# SIM900_schematic.net
KiCad netlist of a schematic drawn in EAGLE
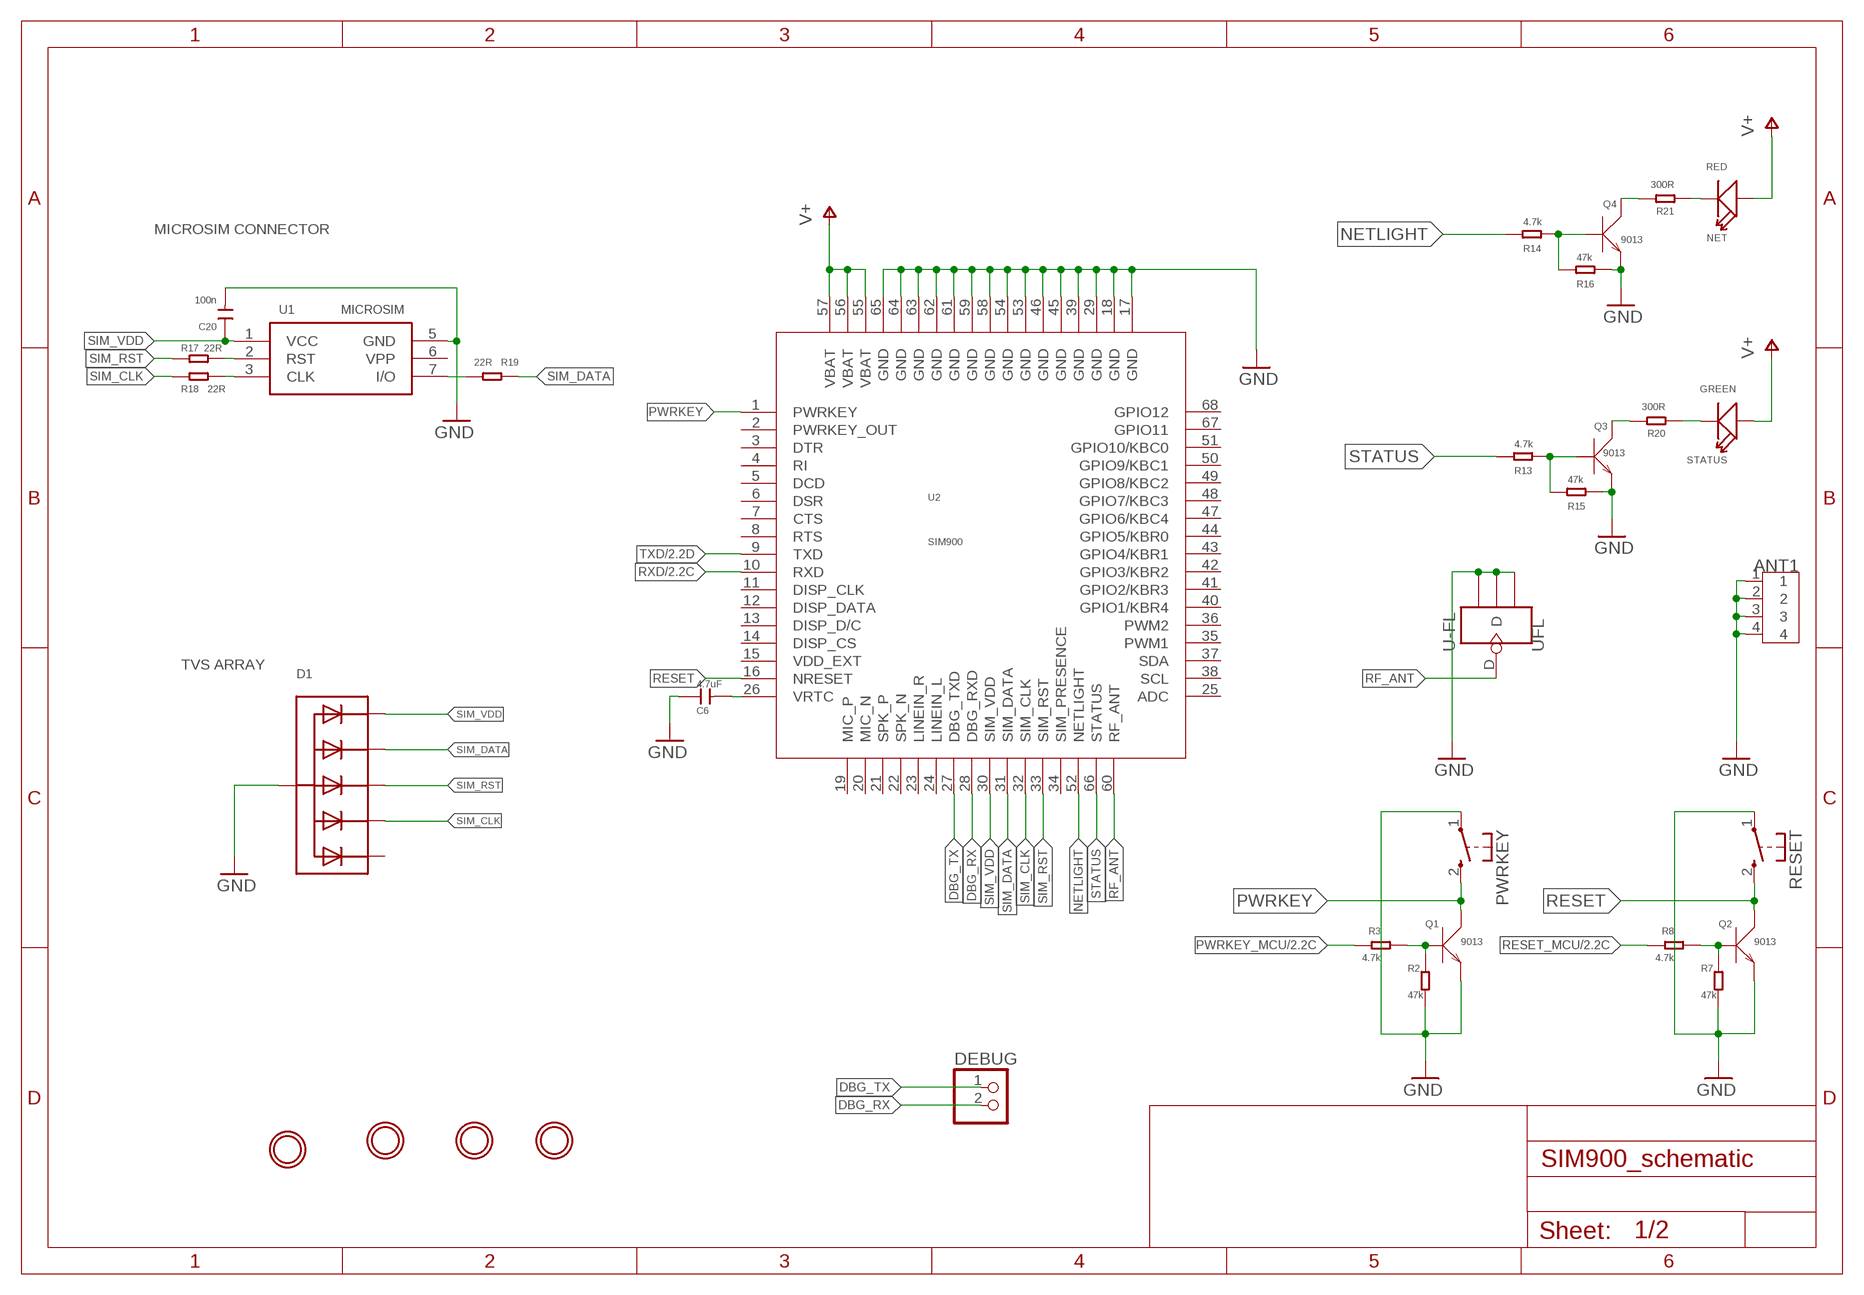
[diagram p0: schematic, sheet 1]
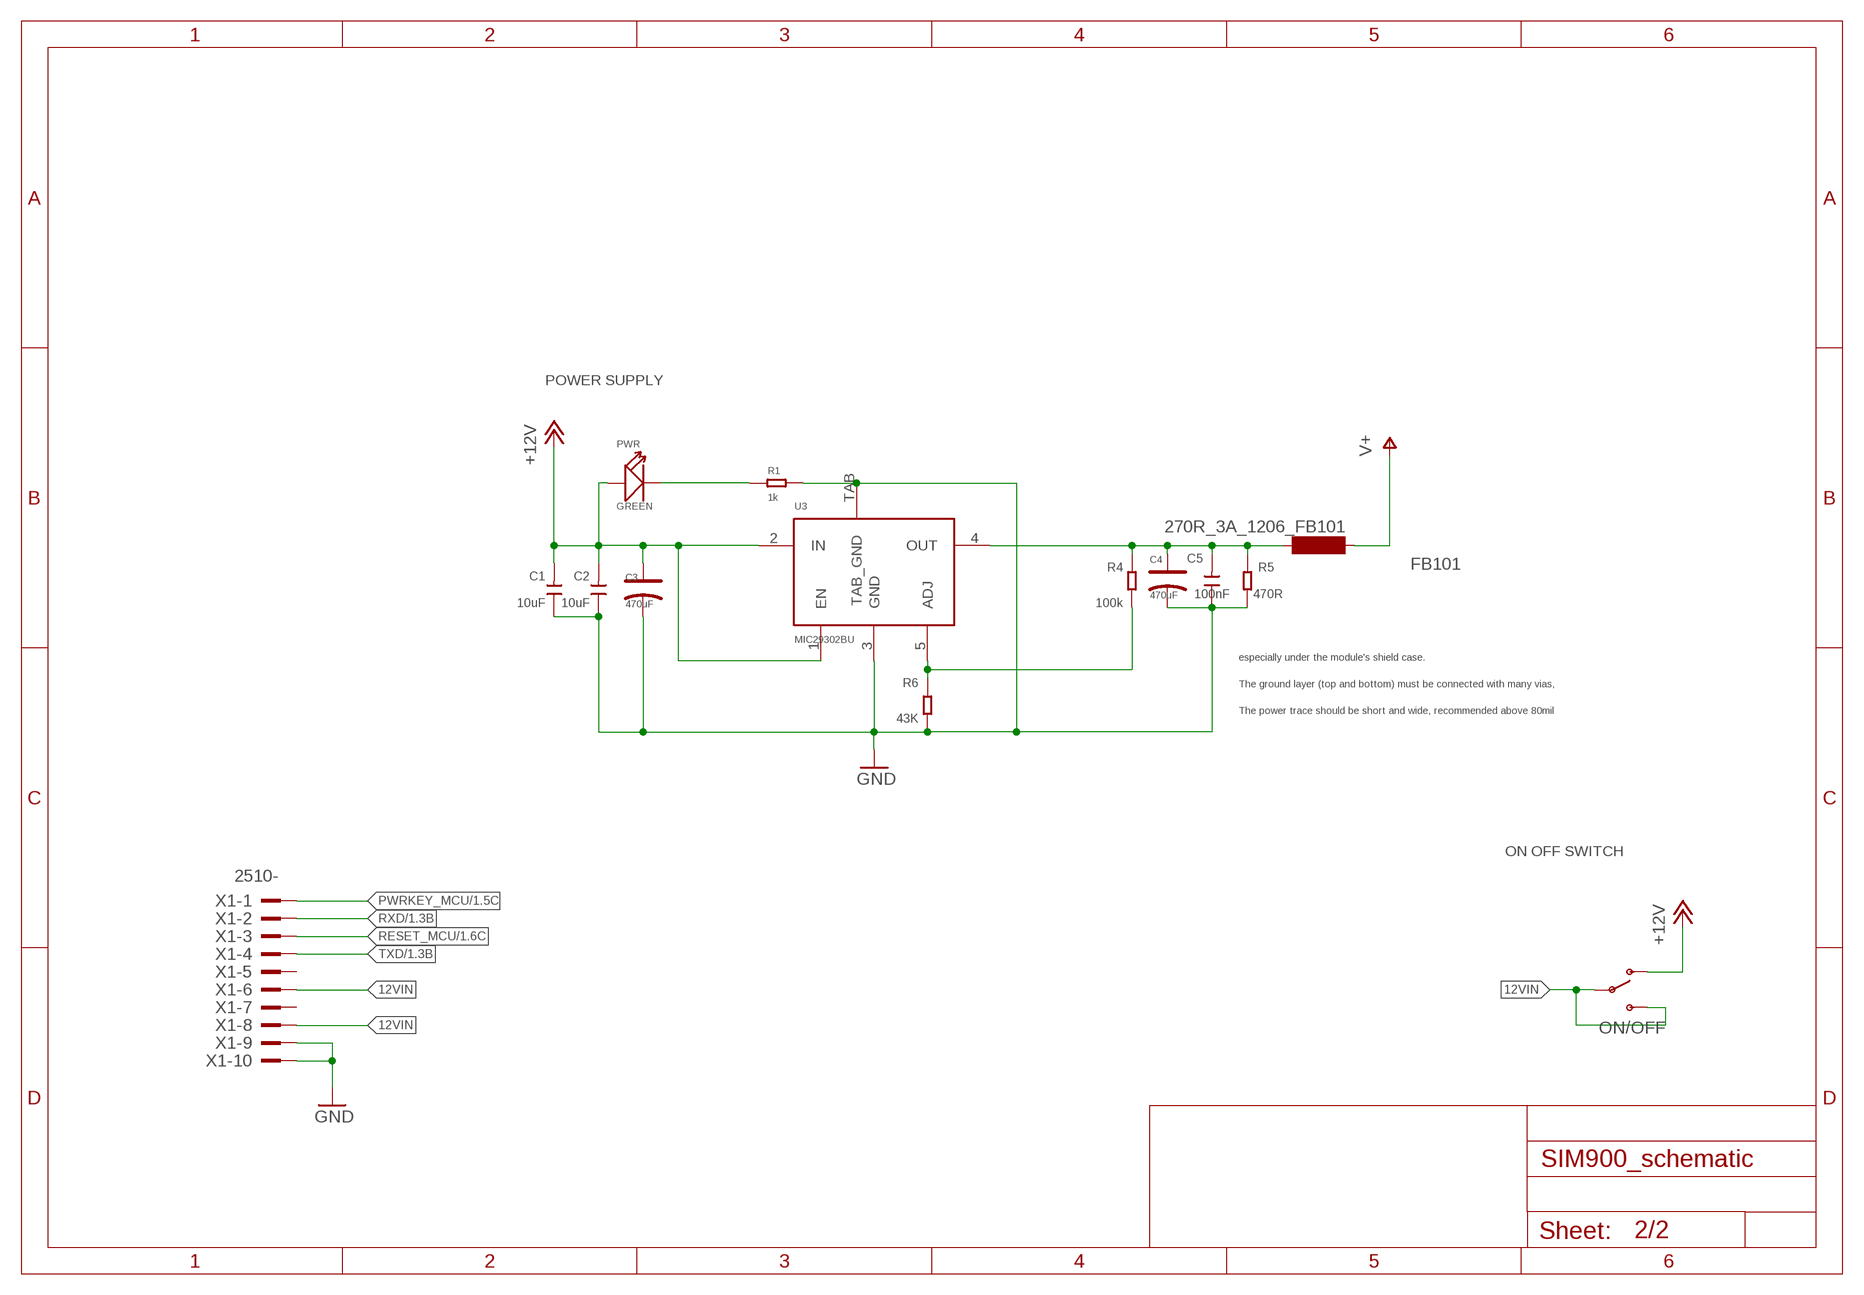
[diagram p1: schematic, sheet 2]

(export (version "E")
  (design (tool "Eeschema 10.0.6"))
  (components
    (comp (ref "C1")
      (value "10uF")
      (footprint "eagle-import:0805")
      (libsource (lib "eagle-import") (part "C-0805"))
    )
    (comp (ref "C2")
      (value "10uF")
      (footprint "eagle-import:0805")
      (libsource (lib "eagle-import") (part "C-0805"))
    )
    (comp (ref "C3")
      (value "470uF")
      (footprint "eagle-import:AVX_D")
      (libsource (lib "eagle-import") (part "006-CAP_AVX_D"))
    )
    (comp (ref "C4")
      (value "470uF")
      (footprint "eagle-import:AVX_D")
      (libsource (lib "eagle-import") (part "006-CAP_AVX_D"))
    )
    (comp (ref "C5")
      (value "100nF")
      (footprint "eagle-import:0805")
      (libsource (lib "eagle-import") (part "C-0805"))
    )
    (comp (ref "FB101")
      (value "270R_3A_1206_FB101")
      (footprint "eagle-import:SM-1206")
      (libsource (lib "eagle-import") (part "SM-1206"))
    )
    (comp (ref "ON/OFF")
      (value "SWITCH-SPDTPTH")
      (footprint "eagle-import:SWITCH-SPDT")
      (libsource (lib "eagle-import") (part "SWITCH-SPDTPTH"))
    )
    (comp (ref "PWR")
      (value "GREEN")
      (footprint "eagle-import:D0805")
      (libsource (lib "eagle-import") (part "007-LED0805"))
    )
    (comp (ref "R1")
      (value "1k")
      (footprint "eagle-import:0805")
      (libsource (lib "eagle-import") (part "R-0805"))
    )
    (comp (ref "R4")
      (value "100k")
      (footprint "eagle-import:0805")
      (libsource (lib "eagle-import") (part "R-0805"))
    )
    (comp (ref "R5")
      (value "470R")
      (footprint "eagle-import:0805")
      (libsource (lib "eagle-import") (part "R-0805"))
    )
    (comp (ref "R6")
      (value "43K")
      (footprint "eagle-import:0805")
      (libsource (lib "eagle-import") (part "R-0805"))
    )
    (comp (ref "U3")
      (value "MIC29302BU")
      (footprint "eagle-import:TO-263")
      (libsource (lib "eagle-import") (part "MIC29302BU"))
    )
    (comp (ref "X1")
      (value "2510-")
      (footprint "eagle-import:PAK100_2500-10")
      (fields (field (name "MF") "3M") (field (name "MPN") "2510-6002UB"))
      (libsource (lib "eagle-import") (part "2510-"))
    )
    (comp (ref "ANT1")
      (value "ANTENNA-SMA-IPX")
      (footprint "eagle-import:SMA-TO-IPX")
      (libsource (lib "eagle-import") (part "ANTENNA-SMA-IPX"))
    )
    (comp (ref "C6")
      (value "4.7uF")
      (footprint "eagle-import:0805")
      (libsource (lib "eagle-import") (part "C-0805"))
    )
    (comp (ref "C20")
      (value "100n")
      (footprint "eagle-import:0805")
      (libsource (lib "eagle-import") (part "C-0805"))
    )
    (comp (ref "D1")
      (value "TVSARRAY_5LANE")
      (footprint "eagle-import:SOT363")
      (libsource (lib "eagle-import") (part "TVSARRAY_5LANE"))
    )
    (comp (ref "DEBUG")
      (value "PINHD-1X2")
      (footprint "eagle-import:1X02")
      (libsource (lib "eagle-import") (part "PINHD-1X2"))
    )
    (comp (ref "NET")
      (value "RED")
      (footprint "eagle-import:LED-0805")
      (libsource (lib "eagle-import") (part "LED'0805'"))
    )
    (comp (ref "PWRKEY")
      (value "KSS-2EG4430")
      (footprint "eagle-import:KSS-2EG4430")
      (libsource (lib "eagle-import") (part "KSS-2EG4430"))
    )
    (comp (ref "Q1")
      (value "9013")
      (footprint "eagle-import:SOT23")
      (libsource (lib "eagle-import") (part "TRANSISTOR-NPN-SOT23"))
    )
    (comp (ref "Q2")
      (value "9013")
      (footprint "eagle-import:SOT23")
      (libsource (lib "eagle-import") (part "TRANSISTOR-NPN-SOT23"))
    )
    (comp (ref "Q3")
      (value "9013")
      (footprint "eagle-import:SOT23")
      (libsource (lib "eagle-import") (part "TRANSISTOR-NPN-SOT23"))
    )
    (comp (ref "Q4")
      (value "9013")
      (footprint "eagle-import:SOT23")
      (libsource (lib "eagle-import") (part "TRANSISTOR-NPN-SOT23"))
    )
    (comp (ref "R2")
      (value "47k")
      (footprint "eagle-import:0805")
      (libsource (lib "eagle-import") (part "R-0805"))
    )
    (comp (ref "R3")
      (value "4.7k")
      (footprint "eagle-import:0805")
      (libsource (lib "eagle-import") (part "R-0805"))
    )
    (comp (ref "R7")
      (value "47k")
      (footprint "eagle-import:0805")
      (libsource (lib "eagle-import") (part "R-0805"))
    )
    (comp (ref "R8")
      (value "4.7k")
      (footprint "eagle-import:0805")
      (libsource (lib "eagle-import") (part "R-0805"))
    )
    (comp (ref "R13")
      (value "4.7k")
      (footprint "eagle-import:0805")
      (libsource (lib "eagle-import") (part "R-0805"))
    )
    (comp (ref "R14")
      (value "4.7k")
      (footprint "eagle-import:0805")
      (libsource (lib "eagle-import") (part "R-0805"))
    )
    (comp (ref "R15")
      (value "47k")
      (footprint "eagle-import:0805")
      (libsource (lib "eagle-import") (part "R-0805"))
    )
    (comp (ref "R16")
      (value "47k")
      (footprint "eagle-import:0805")
      (libsource (lib "eagle-import") (part "R-0805"))
    )
    (comp (ref "R17")
      (value "22R")
      (footprint "eagle-import:0805")
      (libsource (lib "eagle-import") (part "R-0805"))
    )
    (comp (ref "R18")
      (value "22R")
      (footprint "eagle-import:0805")
      (libsource (lib "eagle-import") (part "R-0805"))
    )
    (comp (ref "R19")
      (value "22R")
      (footprint "eagle-import:0805")
      (libsource (lib "eagle-import") (part "R-0805"))
    )
    (comp (ref "R20")
      (value "300R")
      (footprint "eagle-import:0805")
      (libsource (lib "eagle-import") (part "R-0805"))
    )
    (comp (ref "R21")
      (value "300R")
      (footprint "eagle-import:0805")
      (libsource (lib "eagle-import") (part "R-0805"))
    )
    (comp (ref "RESET")
      (value "KSS-2EG4430")
      (footprint "eagle-import:KSS-2EG4430")
      (libsource (lib "eagle-import") (part "KSS-2EG4430"))
    )
    (comp (ref "STATUS")
      (value "GREEN")
      (footprint "eagle-import:LED-0805")
      (libsource (lib "eagle-import") (part "LED'0805'"))
    )
    (comp (ref "U$1")
      (value "MOUNTINGHOLE3.0THIN")
      (footprint "eagle-import:MOUNTINGHOLE_3.0_PLATEDTHIN")
      (libsource (lib "eagle-import") (part "MOUNTINGHOLE3.0THIN"))
    )
    (comp (ref "U$2")
      (value "MOUNTINGHOLE3.0THIN")
      (footprint "eagle-import:MOUNTINGHOLE_3.0_PLATEDTHIN")
      (libsource (lib "eagle-import") (part "MOUNTINGHOLE3.0THIN"))
    )
    (comp (ref "U$3")
      (value "MOUNTINGHOLE3.0THIN")
      (footprint "eagle-import:MOUNTINGHOLE_3.0_PLATEDTHIN")
      (libsource (lib "eagle-import") (part "MOUNTINGHOLE3.0THIN"))
    )
    (comp (ref "U$4")
      (value "MOUNTINGHOLE3.0THIN")
      (footprint "eagle-import:MOUNTINGHOLE_3.0_PLATEDTHIN")
      (libsource (lib "eagle-import") (part "MOUNTINGHOLE3.0THIN"))
    )
    (comp (ref "U1")
      (value "MICROSIM")
      (footprint "eagle-import:MICROSIM")
      (libsource (lib "eagle-import") (part "MICROSIM"))
    )
    (comp (ref "U2")
      (value "SIM900")
      (footprint "eagle-import:SIM900")
      (libsource (lib "eagle-import") (part "SIM900"))
    )
    (comp (ref "UFL")
      (value "U-FL")
      (footprint "eagle-import:4P-U-FL")
      (libsource (lib "eagle-import") (part "ANTENNA-U-FL"))
    )
  )
  (nets
    (net (code "1") (name "+12V") (class "Default")
      (node (ref "C1") (pin "2") (pinfunction "2_2") (pintype "passive"))
      (node (ref "C2") (pin "2") (pinfunction "2_2") (pintype "passive"))
      (node (ref "C3") (pin "+") (pinfunction "+_+") (pintype "passive"))
      (node (ref "ON/OFF") (pin "1") (pinfunction "O_1") (pintype "passive"))
      (node (ref "PWR") (pin "+") (pinfunction "+_+") (pintype "passive"))
      (node (ref "U3") (pin "1") (pinfunction "EN_1") (pintype "bidirectional"))
      (node (ref "U3") (pin "2") (pinfunction "IN_2") (pintype "bidirectional"))
    )
    (net (code "2") (name "12VIN") (class "Default")
      (node (ref "ON/OFF") (pin "2") (pinfunction "P_2") (pintype "passive"))
      (node (ref "ON/OFF") (pin "3") (pinfunction "S_3") (pintype "passive"))
      (node (ref "X1") (pin "6") (pinfunction "KL_6") (pintype "passive"))
      (node (ref "X1") (pin "8") (pinfunction "KL_8") (pintype "passive"))
    )
    (net (code "3") (name "DBG_RX") (class "Default")
      (node (ref "DEBUG") (pin "2") (pinfunction "2_2") (pintype "passive"))
      (node (ref "U2") (pin "28") (pinfunction "DBG_RXD_28") (pintype "input"))
    )
    (net (code "4") (name "DBG_TX") (class "Default")
      (node (ref "DEBUG") (pin "1") (pinfunction "1_1") (pintype "passive"))
      (node (ref "U2") (pin "27") (pinfunction "DBG_TXD_27") (pintype "output"))
    )
    (net (code "5") (name "GND") (class "Default")
      (node (ref "ANT1") (pin "1") (pinfunction "1_1") (pintype "bidirectional"))
      (node (ref "ANT1") (pin "2") (pinfunction "2_2") (pintype "bidirectional"))
      (node (ref "ANT1") (pin "3") (pinfunction "3_3") (pintype "bidirectional"))
      (node (ref "ANT1") (pin "4") (pinfunction "4_4") (pintype "bidirectional"))
      (node (ref "C1") (pin "1") (pinfunction "1_1") (pintype "passive"))
      (node (ref "C2") (pin "1") (pinfunction "1_1") (pintype "passive"))
      (node (ref "C20") (pin "2") (pinfunction "2_2") (pintype "passive"))
      (node (ref "C3") (pin "-") (pinfunction "-_-") (pintype "passive"))
      (node (ref "C4") (pin "-") (pinfunction "-_-") (pintype "passive"))
      (node (ref "C5") (pin "1") (pinfunction "1_1") (pintype "passive"))
      (node (ref "C6") (pin "1") (pinfunction "1_1") (pintype "passive"))
      (node (ref "D1") (pin "2") (pinfunction "A_2") (pintype "passive"))
      (node (ref "PWRKEY") (pin "1") (pinfunction "P_1") (pintype "passive"))
      (node (ref "Q1") (pin "2") (pinfunction "E_2") (pintype "passive"))
      (node (ref "Q2") (pin "2") (pinfunction "E_2") (pintype "passive"))
      (node (ref "Q3") (pin "2") (pinfunction "E_2") (pintype "passive"))
      (node (ref "Q4") (pin "2") (pinfunction "E_2") (pintype "passive"))
      (node (ref "R1") (pin "2") (pinfunction "2_2") (pintype "passive"))
      (node (ref "R15") (pin "2") (pinfunction "2_2") (pintype "passive"))
      (node (ref "R16") (pin "2") (pinfunction "2_2") (pintype "passive"))
      (node (ref "R2") (pin "2") (pinfunction "2_2") (pintype "passive"))
      (node (ref "R5") (pin "1") (pinfunction "1_1") (pintype "passive"))
      (node (ref "R6") (pin "1") (pinfunction "1_1") (pintype "passive"))
      (node (ref "R7") (pin "2") (pinfunction "2_2") (pintype "passive"))
      (node (ref "RESET") (pin "1") (pinfunction "P_1") (pintype "passive"))
      (node (ref "U1") (pin "5") (pinfunction "GND_5") (pintype "bidirectional"))
      (node (ref "U2") (pin "17") (pinfunction "GND_17") (pintype "power_in"))
      (node (ref "U2") (pin "18") (pinfunction "GND_18") (pintype "power_in"))
      (node (ref "U2") (pin "29") (pinfunction "GND_29") (pintype "power_in"))
      (node (ref "U2") (pin "39") (pinfunction "GND_39") (pintype "power_in"))
      (node (ref "U2") (pin "45") (pinfunction "GND_45") (pintype "power_in"))
      (node (ref "U2") (pin "46") (pinfunction "GND_46") (pintype "power_in"))
      (node (ref "U2") (pin "53") (pinfunction "GND_53") (pintype "power_in"))
      (node (ref "U2") (pin "54") (pinfunction "GND_54") (pintype "power_in"))
      (node (ref "U2") (pin "58") (pinfunction "GND_58") (pintype "power_in"))
      (node (ref "U2") (pin "59") (pinfunction "GND_59") (pintype "power_in"))
      (node (ref "U2") (pin "61") (pinfunction "GND_61") (pintype "power_in"))
      (node (ref "U2") (pin "62") (pinfunction "GND_62") (pintype "power_in"))
      (node (ref "U2") (pin "63") (pinfunction "GND_63") (pintype "power_in"))
      (node (ref "U2") (pin "64") (pinfunction "GND_64") (pintype "power_in"))
      (node (ref "U2") (pin "65") (pinfunction "GND_65") (pintype "power_in"))
      (node (ref "U3") (pin "3") (pinfunction "GND_3") (pintype "bidirectional"))
      (node (ref "U3") (pin "TAB") (pinfunction "TAB_GND_TAB") (pintype "bidirectional"))
      (node (ref "UFL") (pin "GND1") (pinfunction "GND1_GND1") (pintype "bidirectional"))
      (node (ref "UFL") (pin "GND2") (pinfunction "GND2_GND2") (pintype "bidirectional"))
      (node (ref "UFL") (pin "GND3") (pinfunction "GND3_GND3") (pintype "bidirectional"))
      (node (ref "X1") (pin "10") (pinfunction "KL_10") (pintype "passive"))
      (node (ref "X1") (pin "9") (pinfunction "KL_9") (pintype "passive"))
    )
    (net (code "6") (name "NETLIGHT") (class "Default")
      (node (ref "R14") (pin "1") (pinfunction "1_1") (pintype "passive"))
      (node (ref "U2") (pin "52") (pinfunction "NETLIGHT_52") (pintype "output"))
    )
    (net (code "7") (name "Net-(NET-Pad-)") (class "Default")
      (node (ref "NET") (pin "-") (pinfunction "-_-") (pintype "passive"))
      (node (ref "R21") (pin "1") (pinfunction "1_1") (pintype "passive"))
    )
    (net (code "8") (name "Net-(PWR-Pad-)") (class "Default")
      (node (ref "PWR") (pin "-") (pinfunction "-_-") (pintype "passive"))
      (node (ref "R1") (pin "1") (pinfunction "1_1") (pintype "passive"))
    )
    (net (code "9") (name "Net-(Q1-B)") (class "Default")
      (node (ref "Q1") (pin "1") (pinfunction "B_1") (pintype "passive"))
      (node (ref "R2") (pin "1") (pinfunction "1_1") (pintype "passive"))
      (node (ref "R3") (pin "2") (pinfunction "2_2") (pintype "passive"))
    )
    (net (code "10") (name "Net-(Q2-B)") (class "Default")
      (node (ref "Q2") (pin "1") (pinfunction "B_1") (pintype "passive"))
      (node (ref "R7") (pin "1") (pinfunction "1_1") (pintype "passive"))
      (node (ref "R8") (pin "2") (pinfunction "2_2") (pintype "passive"))
    )
    (net (code "11") (name "Net-(Q3-B)") (class "Default")
      (node (ref "Q3") (pin "1") (pinfunction "B_1") (pintype "passive"))
      (node (ref "R13") (pin "2") (pinfunction "2_2") (pintype "passive"))
      (node (ref "R15") (pin "1") (pinfunction "1_1") (pintype "passive"))
    )
    (net (code "12") (name "Net-(Q3-C)") (class "Default")
      (node (ref "Q3") (pin "3") (pinfunction "C_3") (pintype "passive"))
      (node (ref "R20") (pin "2") (pinfunction "2_2") (pintype "passive"))
    )
    (net (code "13") (name "Net-(Q4-B)") (class "Default")
      (node (ref "Q4") (pin "1") (pinfunction "B_1") (pintype "passive"))
      (node (ref "R14") (pin "2") (pinfunction "2_2") (pintype "passive"))
      (node (ref "R16") (pin "1") (pinfunction "1_1") (pintype "passive"))
    )
    (net (code "14") (name "Net-(Q4-C)") (class "Default")
      (node (ref "Q4") (pin "3") (pinfunction "C_3") (pintype "passive"))
      (node (ref "R21") (pin "2") (pinfunction "2_2") (pintype "passive"))
    )
    (net (code "15") (name "Net-(R20-Pad1)") (class "Default")
      (node (ref "R20") (pin "1") (pinfunction "1_1") (pintype "passive"))
      (node (ref "STATUS") (pin "-") (pinfunction "-_-") (pintype "passive"))
    )
    (net (code "16") (name "Net-(U1-CLK)") (class "Default")
      (node (ref "R18") (pin "1") (pinfunction "1_1") (pintype "passive"))
      (node (ref "U1") (pin "3") (pinfunction "CLK_3") (pintype "bidirectional"))
    )
    (net (code "17") (name "Net-(U1-I{slash}O)") (class "Default")
      (node (ref "R19") (pin "2") (pinfunction "2_2") (pintype "passive"))
      (node (ref "U1") (pin "7") (pinfunction "I/O_7") (pintype "bidirectional"))
    )
    (net (code "18") (name "Net-(U1-RST)") (class "Default")
      (node (ref "R17") (pin "1") (pinfunction "1_1") (pintype "passive"))
      (node (ref "U1") (pin "2") (pinfunction "RST_2") (pintype "bidirectional"))
    )
    (net (code "19") (name "Net-(U2-VRTC)") (class "Default")
      (node (ref "C6") (pin "2") (pinfunction "2_2") (pintype "passive"))
      (node (ref "U2") (pin "26") (pinfunction "VRTC_26") (pintype "bidirectional"))
    )
    (net (code "20") (name "Net-(U3-ADJ)") (class "Default")
      (node (ref "R4") (pin "1") (pinfunction "1_1") (pintype "passive"))
      (node (ref "R6") (pin "2") (pinfunction "2_2") (pintype "passive"))
      (node (ref "U3") (pin "5") (pinfunction "ADJ_5") (pintype "bidirectional"))
    )
    (net (code "21") (name "Net-(U3-OUT)") (class "Default")
      (node (ref "C4") (pin "+") (pinfunction "+_+") (pintype "passive"))
      (node (ref "C5") (pin "2") (pinfunction "2_2") (pintype "passive"))
      (node (ref "FB101") (pin "2") (pinfunction "2_2") (pintype "passive"))
      (node (ref "R4") (pin "2") (pinfunction "2_2") (pintype "passive"))
      (node (ref "R5") (pin "2") (pinfunction "2_2") (pintype "passive"))
      (node (ref "U3") (pin "4") (pinfunction "OUT_4") (pintype "bidirectional"))
    )
    (net (code "22") (name "PWRKEY") (class "Default")
      (node (ref "PWRKEY") (pin "2") (pinfunction "S_2") (pintype "passive"))
      (node (ref "Q1") (pin "3") (pinfunction "C_3") (pintype "passive"))
      (node (ref "U2") (pin "1") (pinfunction "PWRKEY_1") (pintype "input"))
    )
    (net (code "23") (name "PWRKEY_MCU") (class "Default")
      (node (ref "R3") (pin "1") (pinfunction "1_1") (pintype "passive"))
      (node (ref "X1") (pin "1") (pinfunction "KL_1") (pintype "passive"))
    )
    (net (code "24") (name "RESET") (class "Default")
      (node (ref "Q2") (pin "3") (pinfunction "C_3") (pintype "passive"))
      (node (ref "RESET") (pin "2") (pinfunction "S_2") (pintype "passive"))
      (node (ref "U2") (pin "16") (pinfunction "NRESET_16") (pintype "input"))
    )
    (net (code "25") (name "RESET_MCU") (class "Default")
      (node (ref "R8") (pin "1") (pinfunction "1_1") (pintype "passive"))
      (node (ref "X1") (pin "3") (pinfunction "KL_3") (pintype "passive"))
    )
    (net (code "26") (name "RF_ANT") (class "Default")
      (node (ref "U2") (pin "60") (pinfunction "RF_ANT_60") (pintype "bidirectional"))
      (node (ref "UFL") (pin "D") (pinfunction "D_D") (pintype "bidirectional"))
    )
    (net (code "27") (name "RXD") (class "Default")
      (node (ref "U2") (pin "10") (pinfunction "RXD_10") (pintype "input"))
      (node (ref "X1") (pin "2") (pinfunction "KL_2") (pintype "passive"))
    )
    (net (code "28") (name "SIM_CLK") (class "Default")
      (node (ref "D1") (pin "5") (pinfunction "C4_5") (pintype "passive"))
      (node (ref "R18") (pin "2") (pinfunction "2_2") (pintype "passive"))
      (node (ref "U2") (pin "32") (pinfunction "SIM_CLK_32") (pintype "output"))
    )
    (net (code "29") (name "SIM_DATA") (class "Default")
      (node (ref "D1") (pin "3") (pinfunction "C2_3") (pintype "passive"))
      (node (ref "R19") (pin "1") (pinfunction "1_1") (pintype "passive"))
      (node (ref "U2") (pin "31") (pinfunction "SIM_DATA_31") (pintype "bidirectional"))
    )
    (net (code "30") (name "SIM_RST") (class "Default")
      (node (ref "D1") (pin "4") (pinfunction "C3_4") (pintype "passive"))
      (node (ref "R17") (pin "2") (pinfunction "2_2") (pintype "passive"))
      (node (ref "U2") (pin "33") (pinfunction "SIM_RST_33") (pintype "output"))
    )
    (net (code "31") (name "SIM_VDD") (class "Default")
      (node (ref "C20") (pin "1") (pinfunction "1_1") (pintype "passive"))
      (node (ref "D1") (pin "1") (pinfunction "C1_1") (pintype "passive"))
      (node (ref "U1") (pin "1") (pinfunction "VCC_1") (pintype "bidirectional"))
      (node (ref "U2") (pin "30") (pinfunction "SIM_VDD_30") (pintype "output"))
    )
    (net (code "32") (name "STATUS") (class "Default")
      (node (ref "R13") (pin "1") (pinfunction "1_1") (pintype "passive"))
      (node (ref "U2") (pin "66") (pinfunction "STATUS_66") (pintype "output"))
    )
    (net (code "33") (name "TXD") (class "Default")
      (node (ref "U2") (pin "9") (pinfunction "TXD_9") (pintype "output"))
      (node (ref "X1") (pin "4") (pinfunction "KL_4") (pintype "passive"))
    )
    (net (code "34") (name "V+") (class "Default")
      (node (ref "FB101") (pin "1") (pinfunction "1_1") (pintype "passive"))
      (node (ref "NET") (pin "+") (pinfunction "+_+") (pintype "passive"))
      (node (ref "STATUS") (pin "+") (pinfunction "+_+") (pintype "passive"))
      (node (ref "U2") (pin "55") (pinfunction "VBAT_55") (pintype "power_in"))
      (node (ref "U2") (pin "56") (pinfunction "VBAT_56") (pintype "power_in"))
      (node (ref "U2") (pin "57") (pinfunction "VBAT_57") (pintype "power_in"))
    )
    (net (code "35") (name "unconnected-(D1-C5-Pad6)") (class "Default")
      (node (ref "D1") (pin "6") (pinfunction "C5_6") (pintype "passive"))
    )
    (net (code "36") (name "unconnected-(U1-VPP-Pad6)") (class "Default")
      (node (ref "U1") (pin "6") (pinfunction "VPP_6") (pintype "bidirectional"))
    )
    (net (code "37") (name "unconnected-(U2-ADC-Pad25)") (class "Default")
      (node (ref "U2") (pin "25") (pinfunction "ADC_25") (pintype "input"))
    )
    (net (code "38") (name "unconnected-(U2-CTS-Pad7)") (class "Default")
      (node (ref "U2") (pin "7") (pinfunction "CTS_7") (pintype "output"))
    )
    (net (code "39") (name "unconnected-(U2-DCD-Pad5)") (class "Default")
      (node (ref "U2") (pin "5") (pinfunction "DCD_5") (pintype "output"))
    )
    (net (code "40") (name "unconnected-(U2-DISP_CLK-Pad11)") (class "Default")
      (node (ref "U2") (pin "11") (pinfunction "DISP_CLK_11") (pintype "output"))
    )
    (net (code "41") (name "unconnected-(U2-DISP_CS-Pad14)") (class "Default")
      (node (ref "U2") (pin "14") (pinfunction "DISP_CS_14") (pintype "output"))
    )
    (net (code "42") (name "unconnected-(U2-DISP_DATA-Pad12)") (class "Default")
      (node (ref "U2") (pin "12") (pinfunction "DISP_DATA_12") (pintype "bidirectional"))
    )
    (net (code "43") (name "unconnected-(U2-DISP_D{slash}C-Pad13)") (class "Default")
      (node (ref "U2") (pin "13") (pinfunction "DISP_D/C_13") (pintype "output"))
    )
    (net (code "44") (name "unconnected-(U2-DSR-Pad6)") (class "Default")
      (node (ref "U2") (pin "6") (pinfunction "DSR_6") (pintype "output"))
    )
    (net (code "45") (name "unconnected-(U2-DTR-Pad3)") (class "Default")
      (node (ref "U2") (pin "3") (pinfunction "DTR_3") (pintype "input"))
    )
    (net (code "46") (name "unconnected-(U2-GPIO1{slash}KBR4-Pad40)") (class "Default")
      (node (ref "U2") (pin "40") (pinfunction "GPIO1/KBR4_40") (pintype "output"))
    )
    (net (code "47") (name "unconnected-(U2-GPIO2{slash}KBR3-Pad41)") (class "Default")
      (node (ref "U2") (pin "41") (pinfunction "GPIO2/KBR3_41") (pintype "output"))
    )
    (net (code "48") (name "unconnected-(U2-GPIO3{slash}KBR2-Pad42)") (class "Default")
      (node (ref "U2") (pin "42") (pinfunction "GPIO3/KBR2_42") (pintype "output"))
    )
    (net (code "49") (name "unconnected-(U2-GPIO4{slash}KBR1-Pad43)") (class "Default")
      (node (ref "U2") (pin "43") (pinfunction "GPIO4/KBR1_43") (pintype "output"))
    )
    (net (code "50") (name "unconnected-(U2-GPIO5{slash}KBR0-Pad44)") (class "Default")
      (node (ref "U2") (pin "44") (pinfunction "GPIO5/KBR0_44") (pintype "output"))
    )
    (net (code "51") (name "unconnected-(U2-GPIO6{slash}KBC4-Pad47)") (class "Default")
      (node (ref "U2") (pin "47") (pinfunction "GPIO6/KBC4_47") (pintype "input"))
    )
    (net (code "52") (name "unconnected-(U2-GPIO7{slash}KBC3-Pad48)") (class "Default")
      (node (ref "U2") (pin "48") (pinfunction "GPIO7/KBC3_48") (pintype "bidirectional"))
    )
    (net (code "53") (name "unconnected-(U2-GPIO8{slash}KBC2-Pad49)") (class "Default")
      (node (ref "U2") (pin "49") (pinfunction "GPIO8/KBC2_49") (pintype "input"))
    )
    (net (code "54") (name "unconnected-(U2-GPIO9{slash}KBC1-Pad50)") (class "Default")
      (node (ref "U2") (pin "50") (pinfunction "GPIO9/KBC1_50") (pintype "input"))
    )
    (net (code "55") (name "unconnected-(U2-GPIO10{slash}KBC0-Pad51)") (class "Default")
      (node (ref "U2") (pin "51") (pinfunction "GPIO10/KBC0_51") (pintype "bidirectional"))
    )
    (net (code "56") (name "unconnected-(U2-GPIO11-Pad67)") (class "Default")
      (node (ref "U2") (pin "67") (pinfunction "GPIO11_67") (pintype "bidirectional"))
    )
    (net (code "57") (name "unconnected-(U2-GPIO12-Pad68)") (class "Default")
      (node (ref "U2") (pin "68") (pinfunction "GPIO12_68") (pintype "bidirectional"))
    )
    (net (code "58") (name "unconnected-(U2-LINEIN_L-Pad24)") (class "Default")
      (node (ref "U2") (pin "24") (pinfunction "LINEIN_L_24") (pintype "input"))
    )
    (net (code "59") (name "unconnected-(U2-LINEIN_R-Pad23)") (class "Default")
      (node (ref "U2") (pin "23") (pinfunction "LINEIN_R_23") (pintype "input"))
    )
    (net (code "60") (name "unconnected-(U2-MIC_N-Pad20)") (class "Default")
      (node (ref "U2") (pin "20") (pinfunction "MIC_N_20") (pintype "input"))
    )
    (net (code "61") (name "unconnected-(U2-MIC_P-Pad19)") (class "Default")
      (node (ref "U2") (pin "19") (pinfunction "MIC_P_19") (pintype "input"))
    )
    (net (code "62") (name "unconnected-(U2-PWM1-Pad35)") (class "Default")
      (node (ref "U2") (pin "35") (pinfunction "PWM1_35") (pintype "output"))
    )
    (net (code "63") (name "unconnected-(U2-PWM2-Pad36)") (class "Default")
      (node (ref "U2") (pin "36") (pinfunction "PWM2_36") (pintype "output"))
    )
    (net (code "64") (name "unconnected-(U2-PWRKEY_OUT-Pad2)") (class "Default")
      (node (ref "U2") (pin "2") (pinfunction "PWRKEY_OUT_2") (pintype "output"))
    )
    (net (code "65") (name "unconnected-(U2-RI-Pad4)") (class "Default")
      (node (ref "U2") (pin "4") (pinfunction "RI_4") (pintype "output"))
    )
    (net (code "66") (name "unconnected-(U2-RTS-Pad8)") (class "Default")
      (node (ref "U2") (pin "8") (pinfunction "RTS_8") (pintype "input"))
    )
    (net (code "67") (name "unconnected-(U2-SCL-Pad38)") (class "Default")
      (node (ref "U2") (pin "38") (pinfunction "SCL_38") (pintype "output"))
    )
    (net (code "68") (name "unconnected-(U2-SDA-Pad37)") (class "Default")
      (node (ref "U2") (pin "37") (pinfunction "SDA_37") (pintype "bidirectional"))
    )
    (net (code "69") (name "unconnected-(U2-SIM_PRESENCE-Pad34)") (class "Default")
      (node (ref "U2") (pin "34") (pinfunction "SIM_PRESENCE_34") (pintype "input"))
    )
    (net (code "70") (name "unconnected-(U2-SPK_N-Pad22)") (class "Default")
      (node (ref "U2") (pin "22") (pinfunction "SPK_N_22") (pintype "output"))
    )
    (net (code "71") (name "unconnected-(U2-SPK_P-Pad21)") (class "Default")
      (node (ref "U2") (pin "21") (pinfunction "SPK_P_21") (pintype "output"))
    )
    (net (code "72") (name "unconnected-(U2-VDD_EXT-Pad15)") (class "Default")
      (node (ref "U2") (pin "15") (pinfunction "VDD_EXT_15") (pintype "output"))
    )
    (net (code "73") (name "unconnected-(X1F-KL-Pad5)") (class "Default")
      (node (ref "X1") (pin "5") (pinfunction "KL_5") (pintype "passive"))
    )
    (net (code "74") (name "unconnected-(X1H-KL-Pad7)") (class "Default")
      (node (ref "X1") (pin "7") (pinfunction "KL_7") (pintype "passive"))
    )
  )
)
